# Placa_2.net
KiCad netlist of a schematic drawn in EAGLE
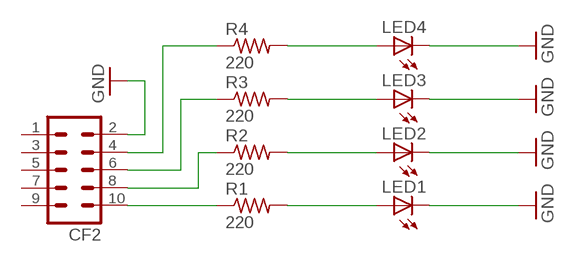
[diagram p0: schematic, sheet 1]

(export (version "E")
  (design (tool "Eeschema 10.0.6"))
  (components
    (comp (ref "CF2")
      (value "ML10")
      (footprint "eagle-import:ML10")
      (libsource (lib "eagle-import") (part "ML10"))
    )
    (comp (ref "LED1")
      (value "LED5MM")
      (footprint "eagle-import:LED5MM")
      (libsource (lib "eagle-import") (part "LED5MM"))
    )
    (comp (ref "LED2")
      (value "LED5MM")
      (footprint "eagle-import:LED5MM")
      (libsource (lib "eagle-import") (part "LED5MM"))
    )
    (comp (ref "LED3")
      (value "LED5MM")
      (footprint "eagle-import:LED5MM")
      (libsource (lib "eagle-import") (part "LED5MM"))
    )
    (comp (ref "LED4")
      (value "LED5MM")
      (footprint "eagle-import:LED5MM")
      (libsource (lib "eagle-import") (part "LED5MM"))
    )
    (comp (ref "R1")
      (value "220")
      (footprint "eagle-import:0204_7")
      (libsource (lib "eagle-import") (part "R-US_0204/7"))
    )
    (comp (ref "R2")
      (value "220")
      (footprint "eagle-import:0204_7")
      (libsource (lib "eagle-import") (part "R-US_0204/7"))
    )
    (comp (ref "R3")
      (value "220")
      (footprint "eagle-import:0204_7")
      (libsource (lib "eagle-import") (part "R-US_0204/7"))
    )
    (comp (ref "R4")
      (value "220")
      (footprint "eagle-import:0204_7")
      (libsource (lib "eagle-import") (part "R-US_0204/7"))
    )
  )
  (nets
    (net (code "1") (name "GND") (class "Default")
      (node (ref "CF2") (pin "2") (pinfunction "2_2") (pintype "passive"))
      (node (ref "LED1") (pin "K") (pinfunction "C_K") (pintype "passive"))
      (node (ref "LED2") (pin "K") (pinfunction "C_K") (pintype "passive"))
      (node (ref "LED3") (pin "K") (pinfunction "C_K") (pintype "passive"))
      (node (ref "LED4") (pin "K") (pinfunction "C_K") (pintype "passive"))
    )
    (net (code "2") (name "Net-(CF2-Pad4)") (class "Default")
      (node (ref "CF2") (pin "4") (pinfunction "4_4") (pintype "passive"))
      (node (ref "R4") (pin "1") (pinfunction "1_1") (pintype "passive"))
    )
    (net (code "3") (name "Net-(CF2-Pad6)") (class "Default")
      (node (ref "CF2") (pin "6") (pinfunction "6_6") (pintype "passive"))
      (node (ref "R3") (pin "1") (pinfunction "1_1") (pintype "passive"))
    )
    (net (code "4") (name "Net-(CF2-Pad8)") (class "Default")
      (node (ref "CF2") (pin "8") (pinfunction "8_8") (pintype "passive"))
      (node (ref "R2") (pin "1") (pinfunction "1_1") (pintype "passive"))
    )
    (net (code "5") (name "Net-(CF2-Pad10)") (class "Default")
      (node (ref "CF2") (pin "10") (pinfunction "10_10") (pintype "passive"))
      (node (ref "R1") (pin "1") (pinfunction "1_1") (pintype "passive"))
    )
    (net (code "6") (name "Net-(LED1-PadA)") (class "Default")
      (node (ref "LED1") (pin "A") (pinfunction "A_A") (pintype "passive"))
      (node (ref "R1") (pin "2") (pinfunction "2_2") (pintype "passive"))
    )
    (net (code "7") (name "Net-(LED2-PadA)") (class "Default")
      (node (ref "LED2") (pin "A") (pinfunction "A_A") (pintype "passive"))
      (node (ref "R2") (pin "2") (pinfunction "2_2") (pintype "passive"))
    )
    (net (code "8") (name "Net-(LED3-PadA)") (class "Default")
      (node (ref "LED3") (pin "A") (pinfunction "A_A") (pintype "passive"))
      (node (ref "R3") (pin "2") (pinfunction "2_2") (pintype "passive"))
    )
    (net (code "9") (name "Net-(LED4-PadA)") (class "Default")
      (node (ref "LED4") (pin "A") (pinfunction "A_A") (pintype "passive"))
      (node (ref "R4") (pin "2") (pinfunction "2_2") (pintype "passive"))
    )
    (net (code "10") (name "unconnected-(CF2-Pad1)") (class "Default")
      (node (ref "CF2") (pin "1") (pinfunction "1_1") (pintype "passive"))
    )
    (net (code "11") (name "unconnected-(CF2-Pad3)") (class "Default")
      (node (ref "CF2") (pin "3") (pinfunction "3_3") (pintype "passive"))
    )
    (net (code "12") (name "unconnected-(CF2-Pad5)") (class "Default")
      (node (ref "CF2") (pin "5") (pinfunction "5_5") (pintype "passive"))
    )
    (net (code "13") (name "unconnected-(CF2-Pad7)") (class "Default")
      (node (ref "CF2") (pin "7") (pinfunction "7_7") (pintype "passive"))
    )
    (net (code "14") (name "unconnected-(CF2-Pad9)") (class "Default")
      (node (ref "CF2") (pin "9") (pinfunction "9_9") (pintype "passive"))
    )
  )
)
